# z0-probe.net
KiCad netlist of a schematic drawn in EAGLE
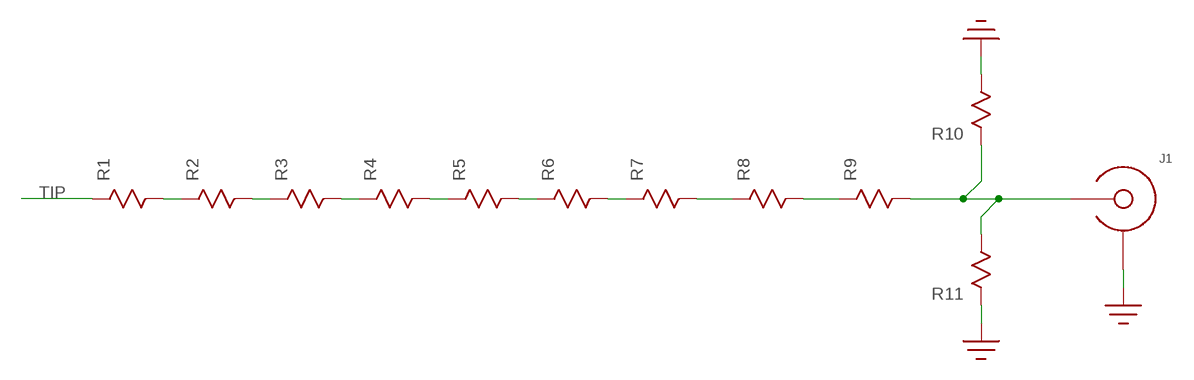
[diagram p0: schematic, sheet 1]

(export (version "E")
  (design (tool "Eeschema 10.0.6"))
  (components
    (comp (ref "J1")
      (value "SMA-EDGE-LAUNCH")
      (footprint "eagle-import:SMA_EDGE_LAUNCH_2L_4020_TAPER_FIXED")
      (libsource (lib "eagle-import") (part "SMA-EDGE-LAUNCH"))
    )
    (comp (ref "R1")
      (value "R0402")
      (footprint "eagle-import:0402")
      (libsource (lib "eagle-import") (part "R0402"))
    )
    (comp (ref "R2")
      (value "R0402")
      (footprint "eagle-import:0402")
      (libsource (lib "eagle-import") (part "R0402"))
    )
    (comp (ref "R3")
      (value "R0402")
      (footprint "eagle-import:0402")
      (libsource (lib "eagle-import") (part "R0402"))
    )
    (comp (ref "R4")
      (value "R0402")
      (footprint "eagle-import:0402")
      (libsource (lib "eagle-import") (part "R0402"))
    )
    (comp (ref "R5")
      (value "R0402")
      (footprint "eagle-import:0402")
      (libsource (lib "eagle-import") (part "R0402"))
    )
    (comp (ref "R6")
      (value "R0402")
      (footprint "eagle-import:0402")
      (libsource (lib "eagle-import") (part "R0402"))
    )
    (comp (ref "R7")
      (value "R0402")
      (footprint "eagle-import:0402")
      (libsource (lib "eagle-import") (part "R0402"))
    )
    (comp (ref "R8")
      (value "R0402")
      (footprint "eagle-import:0402")
      (libsource (lib "eagle-import") (part "R0402"))
    )
    (comp (ref "R9")
      (value "R0402")
      (footprint "eagle-import:0402")
      (libsource (lib "eagle-import") (part "R0402"))
    )
    (comp (ref "R10")
      (value "R0402")
      (footprint "eagle-import:0402")
      (libsource (lib "eagle-import") (part "R0402"))
    )
    (comp (ref "R11")
      (value "R0402")
      (footprint "eagle-import:0402")
      (libsource (lib "eagle-import") (part "R0402"))
    )
  )
  (nets
    (net (code "1") (name "/TIP") (class "Default")
      (node (ref "R1") (pin "1") (pinfunction "P$3_1") (pintype "bidirectional"))
    )
    (net (code "2") (name "GND") (class "Default")
      (node (ref "J1") (pin "BOTTOM_GND") (pinfunction "SHIELD_BOTTOM_GND") (pintype "bidirectional"))
      (node (ref "J1") (pin "GND@1") (pinfunction "SHIELD_GND@1") (pintype "bidirectional"))
      (node (ref "J1") (pin "GND@14") (pinfunction "SHIELD_GND@14") (pintype "bidirectional"))
      (node (ref "J1") (pin "GND@15") (pinfunction "SHIELD_GND@15") (pintype "bidirectional"))
      (node (ref "J1") (pin "GND@16") (pinfunction "SHIELD_GND@16") (pintype "bidirectional"))
      (node (ref "J1") (pin "GND@17") (pinfunction "SHIELD_GND@17") (pintype "bidirectional"))
      (node (ref "J1") (pin "GND@2") (pinfunction "SHIELD_GND@2") (pintype "bidirectional"))
      (node (ref "J1") (pin "GND@3") (pinfunction "SHIELD_GND@3") (pintype "bidirectional"))
      (node (ref "J1") (pin "GND@4") (pinfunction "SHIELD_GND@4") (pintype "bidirectional"))
      (node (ref "J1") (pin "GND@5") (pinfunction "SHIELD_GND@5") (pintype "bidirectional"))
      (node (ref "J1") (pin "GND@6") (pinfunction "SHIELD_GND@6") (pintype "bidirectional"))
      (node (ref "J1") (pin "GND@7") (pinfunction "SHIELD_GND@7") (pintype "bidirectional"))
      (node (ref "J1") (pin "GND@8") (pinfunction "SHIELD_GND@8") (pintype "bidirectional"))
      (node (ref "J1") (pin "GND_PAD1") (pinfunction "SHIELD_GND_PAD1") (pintype "bidirectional"))
      (node (ref "J1") (pin "GND_PAD2") (pinfunction "SHIELD_GND_PAD2") (pintype "bidirectional"))
      (node (ref "J1") (pin "P$1") (pinfunction "SHIELD_P$1") (pintype "bidirectional"))
      (node (ref "J1") (pin "P$2") (pinfunction "SHIELD_P$2") (pintype "bidirectional"))
      (node (ref "R10") (pin "2") (pinfunction "P$4_2") (pintype "bidirectional"))
      (node (ref "R11") (pin "1") (pinfunction "P$3_1") (pintype "bidirectional"))
    )
    (net (code "3") (name "Net-(R1-P$4)") (class "Default")
      (node (ref "R1") (pin "2") (pinfunction "P$4_2") (pintype "bidirectional"))
      (node (ref "R2") (pin "1") (pinfunction "P$3_1") (pintype "bidirectional"))
    )
    (net (code "4") (name "Net-(R2-P$4)") (class "Default")
      (node (ref "R2") (pin "2") (pinfunction "P$4_2") (pintype "bidirectional"))
      (node (ref "R3") (pin "1") (pinfunction "P$3_1") (pintype "bidirectional"))
    )
    (net (code "5") (name "Net-(R3-P$4)") (class "Default")
      (node (ref "R3") (pin "2") (pinfunction "P$4_2") (pintype "bidirectional"))
      (node (ref "R4") (pin "1") (pinfunction "P$3_1") (pintype "bidirectional"))
    )
    (net (code "6") (name "Net-(R4-P$4)") (class "Default")
      (node (ref "R4") (pin "2") (pinfunction "P$4_2") (pintype "bidirectional"))
      (node (ref "R5") (pin "1") (pinfunction "P$3_1") (pintype "bidirectional"))
    )
    (net (code "7") (name "Net-(R5-P$4)") (class "Default")
      (node (ref "R5") (pin "2") (pinfunction "P$4_2") (pintype "bidirectional"))
      (node (ref "R6") (pin "1") (pinfunction "P$3_1") (pintype "bidirectional"))
    )
    (net (code "8") (name "Net-(R6-P$4)") (class "Default")
      (node (ref "R6") (pin "2") (pinfunction "P$4_2") (pintype "bidirectional"))
      (node (ref "R7") (pin "1") (pinfunction "P$3_1") (pintype "bidirectional"))
    )
    (net (code "9") (name "Net-(R7-P$4)") (class "Default")
      (node (ref "R7") (pin "2") (pinfunction "P$4_2") (pintype "bidirectional"))
      (node (ref "R8") (pin "1") (pinfunction "P$3_1") (pintype "bidirectional"))
    )
    (net (code "10") (name "Net-(R8-P$4)") (class "Default")
      (node (ref "R8") (pin "2") (pinfunction "P$4_2") (pintype "bidirectional"))
      (node (ref "R9") (pin "1") (pinfunction "P$3_1") (pintype "bidirectional"))
    )
    (net (code "11") (name "Net-(R10-P$3)") (class "Default")
      (node (ref "J1") (pin "CENTER@1") (pinfunction "CENTER_CENTER@1") (pintype "bidirectional"))
      (node (ref "J1") (pin "P$3") (pinfunction "CENTER_P$3") (pintype "bidirectional"))
      (node (ref "R10") (pin "1") (pinfunction "P$3_1") (pintype "bidirectional"))
      (node (ref "R11") (pin "2") (pinfunction "P$4_2") (pintype "bidirectional"))
      (node (ref "R9") (pin "2") (pinfunction "P$4_2") (pintype "bidirectional"))
    )
  )
)
